# Serial_to_USB_Converter.net
KiCad netlist of a schematic drawn in Altium Designer
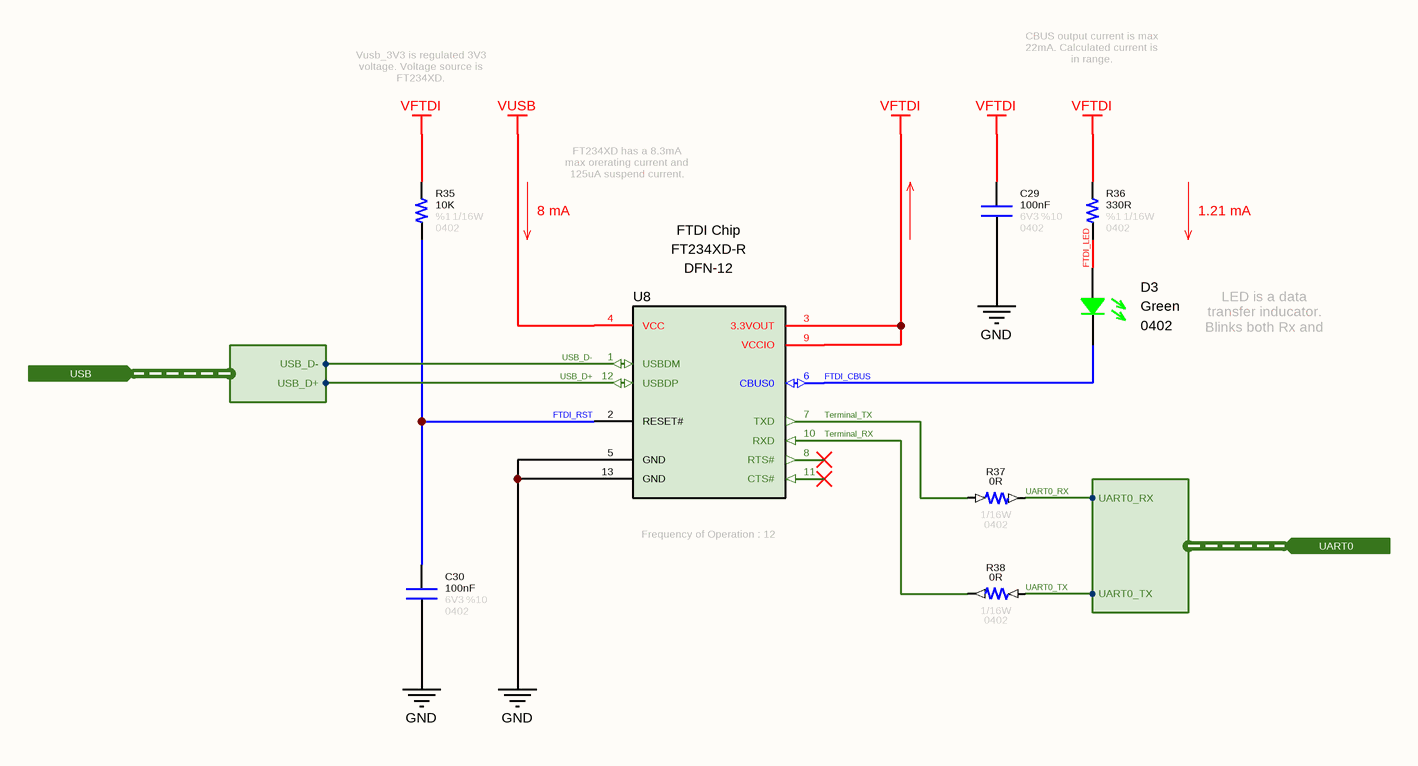
[diagram p0: Serial to USB Converter.SchDoc]

(export (version "E")
  (design (tool "Eeschema 10.0.6"))
  (components
    (comp (ref "C29")
      (value "100nF")
      (footprint "CAPACITOR_0402")
      (description "Capacitor - 100nF [0402-6V3] (Ceramic)")
      (fields
        (field (name "MANUFACTURER PART NUMBER") "04026D104KAT4A")
        (field (name "TOLERANCE") "%10")
        (field (name "VOLTAGE") "6V3")
        (field (name "CASE") "0402")
        (field (name "Comment") "Capacitor - 100nF [0402] (Ceramic)")
      )
      (libsource (lib "P101DA_Library") (part "Capacitor - 100nF [0402-6V3]"))
    )
    (comp (ref "C30")
      (value "100nF")
      (footprint "CAPACITOR_0402")
      (description "Capacitor - 100nF [0402-6V3] (Ceramic)")
      (fields
        (field (name "MANUFACTURER PART NUMBER") "04026D104KAT4A")
        (field (name "TOLERANCE") "%10")
        (field (name "VOLTAGE") "6V3")
        (field (name "CASE") "0402")
        (field (name "Comment") "Capacitor - 100nF [0402] (Ceramic)")
      )
      (libsource (lib "P101DA_Library") (part "Capacitor - 100nF [0402-6V3]"))
    )
    (comp (ref "D3")
      (value "SMD LED (Green)")
      (footprint "LED_0402")
      (description "Standard LEDs - SMD MINI-MOLD ULTRA COMPACT GREEN")
      (fields
        (field (name "MANUFACTURER PART NUMBER") "SML-P12MTT86R")
        (field (name "CASE") "0402")
        (field (name "COLOR") "Green")
      )
      (libsource (lib "P101DA_Library") (part "Diode - LED (0402-Green)"))
    )
    (comp (ref "R35")
      (value "10K")
      (footprint "RESISTOR_0402")
      (description "Thick Film Resistors - SMD 1/16 W 10 KOhm 1%")
      (fields
        (field (name "MANUFACTURER PART NUMBER") "CRCW040210K0FKED")
        (field (name "TOLERANCE") "%1")
        (field (name "CASE") "0402")
        (field (name "POWER") "1/16W")
        (field (name "Comment") "10K - 0402 - %1 - 1/16W")
      )
      (libsource (lib "P101DA_Library") (part "Resistor - 10K [0402]"))
    )
    (comp (ref "R36")
      (value "330R")
      (footprint "RESISTOR_0402")
      (description "Thick Film Resistors - SMD 1/16 W 330 Ohm 1%")
      (fields
        (field (name "MANUFACTURER PART NUMBER") "CRCW0402330RFKED")
        (field (name "CASE") "0402")
        (field (name "TOLERANCE") "%1")
        (field (name "POWER") "1/16W")
        (field (name "Comment") "330R - 0402 - %1 - 1/16W")
      )
      (libsource (lib "P101DA_Library") (part "Resistor - 330R [0402]"))
    )
    (comp (ref "R37")
      (value "0R")
      (footprint "RESISTOR_0402")
      (description "Thick Film Resistors - SMD 1/16 W 0 Ohm")
      (fields
        (field (name "MANUFACTURER PART NUMBER") "CRCW04020000Z0ED")
        (field (name "CASE") "0402")
        (field (name "POWER") "1/16W")
        (field (name "Comment") "0R - 0402 - %1 - 1/16W")
      )
      (libsource (lib "P101DA_Library") (part "Resistor - 0R [0402]"))
    )
    (comp (ref "R38")
      (value "0R")
      (footprint "RESISTOR_0402")
      (description "Thick Film Resistors - SMD 1/16 W 0 Ohm")
      (fields
        (field (name "MANUFACTURER PART NUMBER") "CRCW04020000Z0ED")
        (field (name "CASE") "0402")
        (field (name "POWER") "1/16W")
        (field (name "Comment") "0R - 0402 - %1 - 1/16W")
      )
      (libsource (lib "P101DA_Library") (part "Resistor - 0R [0402]"))
    )
    (comp (ref "U8")
      (value "FT234XD-R")
      (footprint "FT234XD-R")
      (description "USB Interface IC USB to Serial UART Interface")
      (fields
        (field (name "MANUFACTURER NAME") "FTDI Chip")
        (field (name "MANUFACTURER PART NUMBER") "FT234XD-R")
        (field (name "CASE") "DFN-12")
      )
      (libsource (lib "P101DA_Library") (part "IC - FT234XD-R"))
    )
  )
  (nets
    (net (code "3") (name "/FTDI_CBUS") (class "Default")
      (node (ref "D3") (pin "1") (pinfunction "1_1") (pintype "passive"))
      (node (ref "U8") (pin "6") (pinfunction "CBUS0_6") (pintype "bidirectional"))
    )
    (net (code "4") (name "/FTDI_LED") (class "Default")
      (node (ref "D3") (pin "2") (pinfunction "2_2") (pintype "passive"))
      (node (ref "R36") (pin "1") (pinfunction "1_1") (pintype "passive"))
    )
    (net (code "5") (name "/FTDI_RST") (class "Default")
      (node (ref "C30") (pin "2") (pinfunction "2_2") (pintype "passive"))
      (node (ref "R35") (pin "1") (pinfunction "1_1") (pintype "passive"))
      (node (ref "U8") (pin "2") (pinfunction "RESET#_2") (pintype "passive"))
    )
    (net (code "6") (name "/Terminal_RX") (class "Default")
      (node (ref "R38") (pin "2") (pinfunction "2_2") (pintype "input"))
      (node (ref "U8") (pin "10") (pinfunction "RXD_10") (pintype "input"))
    )
    (net (code "7") (name "/Terminal_TX") (class "Default")
      (node (ref "R37") (pin "2") (pinfunction "2_2") (pintype "input"))
      (node (ref "U8") (pin "7") (pinfunction "TXD_7") (pintype "output"))
    )
    (net (code "8") (name "/UART0_RX") (class "Default")
      (node (ref "R37") (pin "1") (pinfunction "1_1") (pintype "output"))
    )
    (net (code "9") (name "/UART0_TX") (class "Default")
      (node (ref "R38") (pin "1") (pinfunction "1_1") (pintype "output"))
    )
    (net (code "10") (name "/USB_D+") (class "Default")
      (node (ref "U8") (pin "12") (pinfunction "USBDP_12") (pintype "bidirectional"))
    )
    (net (code "11") (name "/USB_D-") (class "Default")
      (node (ref "U8") (pin "1") (pinfunction "USBDM_1") (pintype "bidirectional"))
    )
    (net (code "14") (name "GND") (class "Default")
      (node (ref "C29") (pin "1") (pinfunction "1_1") (pintype "passive"))
      (node (ref "C30") (pin "1") (pinfunction "1_1") (pintype "passive"))
      (node (ref "U8") (pin "13") (pinfunction "GND_13") (pintype "power_in"))
      (node (ref "U8") (pin "5") (pinfunction "GND_5") (pintype "power_in"))
    )
    (net (code "15") (name "VFTDI") (class "Default")
      (node (ref "C29") (pin "2") (pinfunction "2_2") (pintype "passive"))
      (node (ref "R35") (pin "2") (pinfunction "2_2") (pintype "passive"))
      (node (ref "R36") (pin "2") (pinfunction "2_2") (pintype "passive"))
      (node (ref "U8") (pin "3") (pinfunction "3.3VOUT_3") (pintype "power_in"))
      (node (ref "U8") (pin "9") (pinfunction "VCCIO_9") (pintype "power_in"))
    )
    (net (code "16") (name "VUSB") (class "Default")
      (node (ref "U8") (pin "4") (pinfunction "VCC_4") (pintype "power_in"))
    )
    (net (code "17") (name "unconnected-(U8-CTS#-Pad11)") (class "Default")
      (node (ref "U8") (pin "11") (pinfunction "CTS#_11") (pintype "input+no_connect"))
    )
    (net (code "18") (name "unconnected-(U8-RTS#-Pad8)") (class "Default")
      (node (ref "U8") (pin "8") (pinfunction "RTS#_8") (pintype "output+no_connect"))
    )
  )
)
